# UWB_R_v1_4.net
KiCad netlist of a schematic drawn in Altium Designer
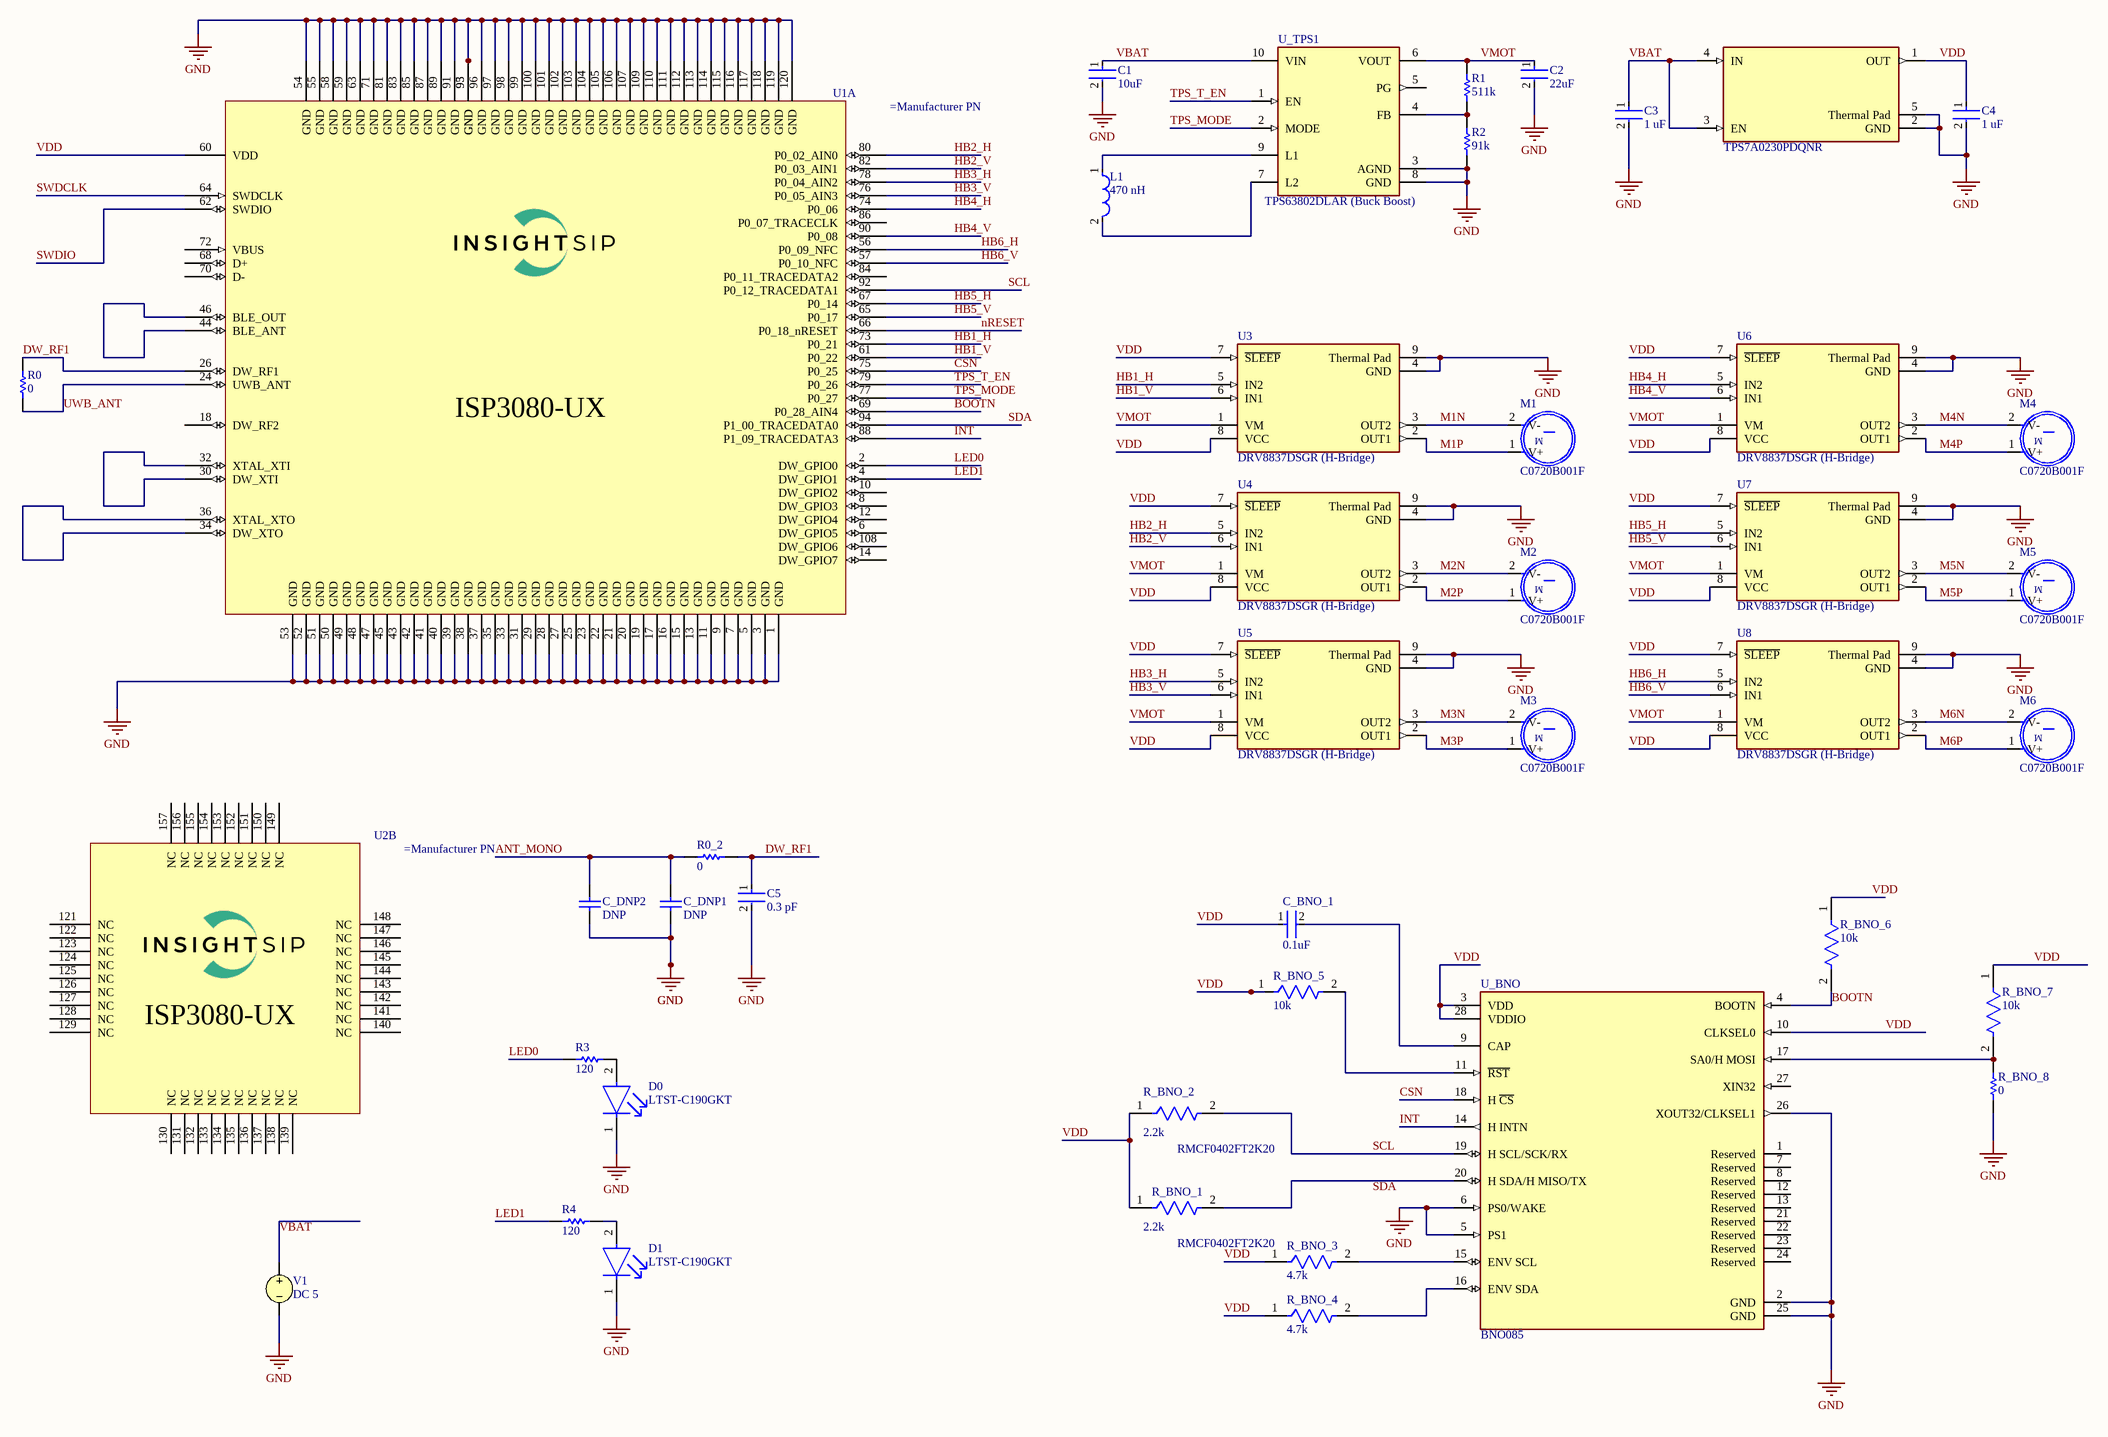
[diagram p0: UWB_R_v1.4.SchDoc]

(export (version "E")
  (design (tool "Eeschema 10.0.6"))
  (components
    (comp (ref "C1")
      (value "10uF")
      (footprint "FP-CL05A106MP5NUNC-MFG")
      (description "CL05A106MP5NUNC CAP CER 10UF 10V X5R 0402")
      (fields
        (field (name "OCTOPART") "https://octopart.com/cl05a106mp5nunc-samsung-22457395")
        (field (name "TOLERANCE") "20%")
      )
      (libsource (lib "Altium Content Vault") (part "b4654b650e69147ec39a6b967a45e02"))
    )
    (comp (ref "C2")
      (value "22uF")
      (footprint "FP-GRM188-0_2-IPC_C")
      (fields (field (name "TOLERANCE") "20%"))
      (libsource (lib "Altium Content Vault") (part "11868f565c42a9108669ba33697ecf6"))
    )
    (comp (ref "C3")
      (value "1 uF")
      (footprint "FP-CL10-IPC_C")
      (description "CL10B105KP8NNNC Cap Ceramic 1uF 10V X7R ±10% Pad SMD 0603 +125°C T/R")
      (fields (field (name "TOLERANCE") "10%"))
      (libsource (lib "Altium Content Vault") (part "b4654b650e69147ec39a6b967a45e02"))
    )
    (comp (ref "C4")
      (value "1 uF")
      (footprint "FP-CL10-IPC_C")
      (description "CL10B105KP8NNNC Cap Ceramic 1uF 10V X7R ±10% Pad SMD 0603 +125°C T/R")
      (fields (field (name "TOLERANCE") "10%"))
      (libsource (lib "Altium Content Vault") (part "b4654b650e69147ec39a6b967a45e02"))
    )
    (comp (ref "C5")
      (value "0.3 pF")
      (footprint "FP-GRM033-0_03-IPC_B")
      (description "GRM0335C1ER30BA01D")
      (libsource (lib "Altium Content Vault") (part "b4654b650e69147ec39a6b967a45e02"))
    )
    (comp (ref "C_BNO_1")
      (value "0.1uF")
      (footprint "FP-0402B104K160CT-IPC_C")
      (description "CAP CER 0.1UF 16V X7R 0402 0402B104K160CT")
      (fields (field (name "TOLERANCE") "10%"))
      (libsource (lib "Altium Content Vault") (part "b4654b650e69147ec39a6b967a45e02"))
    )
    (comp (ref "C_DNP1")
      (value "DNP")
      (footprint "CAPC1005X56X25NL10T15")
      (fields
        (field (name "PART NUMBER") "04025A180KAT2A")
        (field (name "MANUFACTURER") "AVX Interconnect / Elco")
      )
      (libsource (lib "Altium Content Vault") (part "CAP"))
    )
    (comp (ref "C_DNP2")
      (value "DNP")
      (footprint "CAPC1005X56X25NL10T15")
      (fields
        (field (name "PART NUMBER") "04025A180KAT2A")
        (field (name "MANUFACTURER") "AVX Interconnect / Elco")
      )
      (libsource (lib "Altium Content Vault") (part "CAP"))
    )
    (comp (ref "D0")
      (value "LTST-C190GKT")
      (footprint "FP-LTST-C190GKT-MFG")
      (description "LED GREEN CLEAR CHIP SMD")
      (fields (field (name "VOLTAGE") "2V"))
      (libsource (lib "Altium Content Vault") (part "8706943c75ba83719d021d2fdc84c58"))
    )
    (comp (ref "D1")
      (value "LTST-C190GKT")
      (footprint "FP-LTST-C190GKT-MFG")
      (description "LED GREEN CLEAR CHIP SMD")
      (fields (field (name "VOLTAGE") "2V"))
      (libsource (lib "Altium Content Vault") (part "8706943c75ba83719d021d2fdc84c58"))
    )
    (comp (ref "L1")
      (value "470 nH")
      (footprint "FP-CIGT201610-MFG")
      (description "CIGT201610EHR47MNE FIXED IND 470NH 4.8A 22MOHM SMD")
      (fields (field (name "TOLERANCE") "20%"))
      (libsource (lib "Altium Content Vault") (part "725321dda6339637d4d059423bc1c3c"))
    )
    (comp (ref "M1")
      (value "C0720B001F")
      (footprint "XDCR_C0720B001F")
      (description "DC Motor Vibration, ERM 10000 RPM 3VDC")
      (fields (field (name "MF") "Jinlong Machinery"))
      (libsource (lib "C0720B001F") (part "C0720B001F"))
    )
    (comp (ref "M2")
      (value "C0720B001F")
      (footprint "XDCR_C0720B001F")
      (description "DC Motor Vibration, ERM 10000 RPM 3VDC")
      (fields (field (name "MF") "Jinlong Machinery"))
      (libsource (lib "C0720B001F") (part "C0720B001F"))
    )
    (comp (ref "M3")
      (value "C0720B001F")
      (footprint "XDCR_C0720B001F")
      (description "DC Motor Vibration, ERM 10000 RPM 3VDC")
      (fields (field (name "MF") "Jinlong Machinery"))
      (libsource (lib "C0720B001F") (part "C0720B001F"))
    )
    (comp (ref "M4")
      (value "C0720B001F")
      (footprint "XDCR_C0720B001F")
      (description "DC Motor Vibration, ERM 10000 RPM 3VDC")
      (fields (field (name "MF") "Jinlong Machinery"))
      (libsource (lib "C0720B001F") (part "C0720B001F"))
    )
    (comp (ref "M5")
      (value "C0720B001F")
      (footprint "XDCR_C0720B001F")
      (description "DC Motor Vibration, ERM 10000 RPM 3VDC")
      (fields (field (name "MF") "Jinlong Machinery"))
      (libsource (lib "C0720B001F") (part "C0720B001F"))
    )
    (comp (ref "M6")
      (value "C0720B001F")
      (footprint "XDCR_C0720B001F")
      (description "DC Motor Vibration, ERM 10000 RPM 3VDC")
      (fields (field (name "MF") "Jinlong Machinery"))
      (libsource (lib "C0720B001F") (part "C0720B001F"))
    )
    (comp (ref "R0")
      (value "0")
      (footprint "RESC1005X40X25NL05T10")
      (description "RC0402JR-070RL")
      (fields (field (name "MANUFACTURER") "Yageo / Phycomp"))
      (libsource (lib "Altium Content Vault") (part "RES"))
    )
    (comp (ref "R0_2")
      (value "0")
      (footprint "RESC1005X40X25NL05T10")
      (description "RC0402JR-070RL")
      (fields (field (name "MANUFACTURER") "Yageo / Phycomp"))
      (libsource (lib "Altium Content Vault") (part "RES"))
    )
    (comp (ref "R1")
      (value "511k")
      (footprint "RESC1608X55X25ML10T15")
      (description "RC0603FR-07511KL")
      (fields (field (name "MANUFACTURER") "Yageo"))
      (libsource (lib "Altium Content Vault") (part "RES"))
    )
    (comp (ref "R2")
      (value "91k")
      (footprint "RESC0603X26X15NL03T05")
      (description "ERJ1GNF9102C")
      (fields (field (name "MANUFACTURER") "Panasonic"))
      (libsource (lib "Altium Content Vault") (part "RES"))
    )
    (comp (ref "R3")
      (value "120")
      (footprint "RESC2013X50X40ML20T20")
      (description "RG2012N-121-W-T1")
      (fields (field (name "MANUFACTURER") "Susumu"))
      (libsource (lib "Altium Content Vault") (part "RES"))
    )
    (comp (ref "R4")
      (value "120")
      (footprint "RESC2013X50X40ML20T20")
      (description "RG2012N-121-W-T1")
      (fields (field (name "MANUFACTURER") "Susumu"))
      (libsource (lib "Altium Content Vault") (part "RES"))
    )
    (comp (ref "R_BNO_1")
      (value "2.2k")
      (footprint "Stackpole_RMCF0402_IPC_A")
      (description "RES SMD 2.2K OHM 1% 1/16W 0402 RMCF0402FT2K20")
      (fields
        (field (name "PART NUMBER") "RMCF0402FT2K20")
        (field (name "DIGIKEY PART NUMBER") "RMCF0402FT2K20TR-ND")
      )
      (libsource (lib "EEConcierge") (part "RMCF0402FT2K20"))
    )
    (comp (ref "R_BNO_2")
      (value "2.2k")
      (footprint "Stackpole_RMCF0402_IPC_A")
      (description "RES SMD 2.2K OHM 1% 1/16W 0402 RMCF0402FT2K20")
      (fields
        (field (name "PART NUMBER") "RMCF0402FT2K20")
        (field (name "DIGIKEY PART NUMBER") "RMCF0402FT2K20TR-ND")
      )
      (libsource (lib "EEConcierge") (part "RMCF0402FT2K20"))
    )
    (comp (ref "R_BNO_3")
      (value "4.7k")
      (footprint "FP-RC0402-0_4-MFG")
      (description "RC0402JR-074K7L")
      (fields (field (name "TOLERANCE") "5%"))
      (libsource (lib "Altium Content Vault") (part "RC0402JR-074K7L"))
    )
    (comp (ref "R_BNO_4")
      (value "4.7k")
      (footprint "FP-RC0402-0_4-MFG")
      (description "RC0402JR-074K7L")
      (fields (field (name "TOLERANCE") "5%"))
      (libsource (lib "Altium Content Vault") (part "RC0402JR-074K7L"))
    )
    (comp (ref "R_BNO_5")
      (value "10k")
      (footprint "FP-RC0603-0_55-IPC_C")
      (description "RES 10K OHM 1% 1/10W 0603\r\n\r\nRC0603FR-0710KL")
      (fields (field (name "TOLERANCE") "1%"))
      (libsource (lib "Altium Content Vault") (part "1029c3af85768c4190bb7ad29bc67b5"))
    )
    (comp (ref "R_BNO_6")
      (value "10k")
      (footprint "FP-RC0603-0_55-IPC_C")
      (description "RES 10K OHM 1% 1/10W 0603\r\n\r\nRC0603FR-0710KL")
      (fields (field (name "TOLERANCE") "1%"))
      (libsource (lib "Altium Content Vault") (part "1029c3af85768c4190bb7ad29bc67b5"))
    )
    (comp (ref "R_BNO_7")
      (value "10k")
      (footprint "FP-RC0603-0_55-IPC_C")
      (description "RES 10K OHM 1% 1/10W 0603\r\n\r\nRC0603FR-0710KL")
      (fields (field (name "TOLERANCE") "1%"))
      (libsource (lib "Altium Content Vault") (part "1029c3af85768c4190bb7ad29bc67b5"))
    )
    (comp (ref "R_BNO_8")
      (value "0")
      (footprint "RESC1005X40X25NL05T10")
      (description "RC0402JR-070RL")
      (fields (field (name "MANUFACTURER") "Yageo / Phycomp"))
      (libsource (lib "Altium Content Vault") (part "RES"))
    )
    (comp (ref "TPS7A0230PDQNR")
      (value "TPS7A0230PDQNR")
      (footprint "Texas_Instruments_DQN0004A_MFG")
      (description "Linear Voltage Regulator IC, 1 Output, 6-1.5 V to 0.8-5 V (Fixed) Output, 200mA, 4-X2SON (1x1)")
      (fields
        (field (name "DIGIKEY PART NUMBER") "296-TPS7A0230PDQNRCT-ND")
        (field (name "MANUFACTURER") "Texas Instruments")
      )
      (libsource (lib "EEConcierge") (part "TPS7A0230PDQNR"))
    )
    (comp (ref "U1")
      (value "~")
      (footprint "ISP3080-UX")
      (description "BLE & UWB module (Revision C)")
      (libsource (lib "ISP3080C") (part "ISP3080-UX"))
    )
    (comp (ref "U2")
      (value "~")
      (description "BLE & UWB module (Revision C)")
      (libsource (lib "ISP3080C") (part "ISP3080-UX"))
    )
    (comp (ref "U3")
      (value "DRV8837DSGR (H-Bridge)")
      (footprint "FP-DSG0008A-MFG")
      (description "IC MOTOR DRIVER PAR 8WSON")
      (fields
        (field (name "MANUFACTURER PART NUMBER") "DRV8837DSGR")
        (field (name "MANUFACTURER") "Texas Instruments")
      )
      (libsource (lib "Altium Content Vault") (part "0edabe62f55b79d65ef7cb8a22a7164"))
    )
    (comp (ref "U4")
      (value "DRV8837DSGR (H-Bridge)")
      (footprint "FP-DSG0008A-MFG")
      (description "IC MOTOR DRIVER PAR 8WSON")
      (fields
        (field (name "MANUFACTURER PART NUMBER") "DRV8837DSGR")
        (field (name "MANUFACTURER") "Texas Instruments")
      )
      (libsource (lib "Altium Content Vault") (part "0edabe62f55b79d65ef7cb8a22a7164"))
    )
    (comp (ref "U5")
      (value "DRV8837DSGR (H-Bridge)")
      (footprint "FP-DSG0008A-MFG")
      (description "IC MOTOR DRIVER PAR 8WSON")
      (fields
        (field (name "MANUFACTURER PART NUMBER") "DRV8837DSGR")
        (field (name "MANUFACTURER") "Texas Instruments")
      )
      (libsource (lib "Altium Content Vault") (part "0edabe62f55b79d65ef7cb8a22a7164"))
    )
    (comp (ref "U6")
      (value "DRV8837DSGR (H-Bridge)")
      (footprint "FP-DSG0008A-MFG")
      (description "IC MOTOR DRIVER PAR 8WSON")
      (fields
        (field (name "MANUFACTURER PART NUMBER") "DRV8837DSGR")
        (field (name "MANUFACTURER") "Texas Instruments")
      )
      (libsource (lib "Altium Content Vault") (part "0edabe62f55b79d65ef7cb8a22a7164"))
    )
    (comp (ref "U7")
      (value "DRV8837DSGR (H-Bridge)")
      (footprint "FP-DSG0008A-MFG")
      (description "IC MOTOR DRIVER PAR 8WSON")
      (fields
        (field (name "MANUFACTURER PART NUMBER") "DRV8837DSGR")
        (field (name "MANUFACTURER") "Texas Instruments")
      )
      (libsource (lib "Altium Content Vault") (part "0edabe62f55b79d65ef7cb8a22a7164"))
    )
    (comp (ref "U8")
      (value "DRV8837DSGR (H-Bridge)")
      (footprint "FP-DSG0008A-MFG")
      (description "IC MOTOR DRIVER PAR 8WSON")
      (fields
        (field (name "MANUFACTURER PART NUMBER") "DRV8837DSGR")
        (field (name "MANUFACTURER") "Texas Instruments")
      )
      (libsource (lib "Altium Content Vault") (part "0edabe62f55b79d65ef7cb8a22a7164"))
    )
    (comp (ref "U_BNO")
      (value "BNO085")
      (footprint "FP-BNO085-MFG")
      (description "IMU ACCEL/GYRO/MAG I2C 32BIT")
      (fields
        (field (name "OCTOPART") "https://octopart.com/bno085-hillcrest+laboratories-92813482")
        (field (name "MANUFACTURER") "Hillcrest Laboratories, Inc.")
      )
      (libsource (lib "Altium Content Vault") (part "87552c951d161a888c2c69b58ce40bc"))
    )
    (comp (ref "U_TPS1")
      (value "TPS63802DLAR (Buck Boost)")
      (footprint "FP-DLA0010A-MFG")
      (description "IC POWER MANAGEMENT")
      (fields
        (field (name "MANUFACTURER PART NUMBER") "TPS63802DLAR")
        (field (name "OCTOPART") "https://octopart.com/tps63802dlar-texas+instruments-97359678")
      )
      (libsource (lib "Altium Content Vault") (part "f9a6115c6bf72e8ba457236a565d59e"))
    )
    (comp (ref "V1")
      (value "DC 5")
      (description "Voltage Source")
      (fields (field (name "PUBLISHER") "Altium Limited"))
      (libsource (lib "Simulation Generic Components") (part "VSRC"))
    )
  )
  (nets
    (net (code "1") (name "/ANT_MONO") (class "Default")
      (node (ref "C_DNP1") (pin "2") (pinfunction "2_2") (pintype "passive"))
      (node (ref "C_DNP2") (pin "2") (pinfunction "2_2") (pintype "passive"))
      (node (ref "R0_2") (pin "2") (pinfunction "2_2") (pintype "passive"))
    )
    (net (code "2") (name "/BOOTN") (class "Default")
      (node (ref "R_BNO_6") (pin "2") (pinfunction "2_2") (pintype "passive"))
      (node (ref "U1") (pin "69") (pinfunction "P0_28_AIN4_69") (pintype "bidirectional"))
      (node (ref "U_BNO") (pin "4") (pinfunction "BOOTN_4") (pintype "input"))
    )
    (net (code "3") (name "/CSN") (class "Default")
      (node (ref "U1") (pin "75") (pinfunction "P0_25_75") (pintype "bidirectional"))
      (node (ref "U_BNO") (pin "18") (pinfunction "H_~{CS}_18") (pintype "input"))
    )
    (net (code "4") (name "/DW_RF1") (class "Default")
      (node (ref "C5") (pin "1") (pinfunction "1_1") (pintype "passive"))
      (node (ref "R0") (pin "2") (pinfunction "2_2") (pintype "passive"))
      (node (ref "R0_2") (pin "1") (pinfunction "1_1") (pintype "passive"))
      (node (ref "U1") (pin "26") (pinfunction "DW_RF1_26") (pintype "bidirectional"))
    )
    (net (code "5") (name "/HB1_H") (class "Default")
      (node (ref "U1") (pin "73") (pinfunction "P0_21_73") (pintype "bidirectional"))
      (node (ref "U3") (pin "5") (pinfunction "IN2_5") (pintype "input"))
    )
    (net (code "6") (name "/HB1_V") (class "Default")
      (node (ref "U1") (pin "61") (pinfunction "P0_22_61") (pintype "bidirectional"))
      (node (ref "U3") (pin "6") (pinfunction "IN1_6") (pintype "input"))
    )
    (net (code "7") (name "/HB2_H") (class "Default")
      (node (ref "U1") (pin "80") (pinfunction "P0_02_AIN0_80") (pintype "bidirectional"))
      (node (ref "U4") (pin "5") (pinfunction "IN2_5") (pintype "input"))
    )
    (net (code "8") (name "/HB2_V") (class "Default")
      (node (ref "U1") (pin "82") (pinfunction "P0_03_AIN1_82") (pintype "bidirectional"))
      (node (ref "U4") (pin "6") (pinfunction "IN1_6") (pintype "input"))
    )
    (net (code "9") (name "/HB3_H") (class "Default")
      (node (ref "U1") (pin "78") (pinfunction "P0_04_AIN2_78") (pintype "bidirectional"))
      (node (ref "U5") (pin "5") (pinfunction "IN2_5") (pintype "input"))
    )
    (net (code "10") (name "/HB3_V") (class "Default")
      (node (ref "U1") (pin "76") (pinfunction "P0_05_AIN3_76") (pintype "bidirectional"))
      (node (ref "U5") (pin "6") (pinfunction "IN1_6") (pintype "input"))
    )
    (net (code "11") (name "/HB4_H") (class "Default")
      (node (ref "U1") (pin "74") (pinfunction "P0_06_74") (pintype "bidirectional"))
      (node (ref "U6") (pin "5") (pinfunction "IN2_5") (pintype "input"))
    )
    (net (code "12") (name "/HB4_V") (class "Default")
      (node (ref "U1") (pin "90") (pinfunction "P0_08_90") (pintype "bidirectional"))
      (node (ref "U6") (pin "6") (pinfunction "IN1_6") (pintype "input"))
    )
    (net (code "13") (name "/HB5_H") (class "Default")
      (node (ref "U1") (pin "67") (pinfunction "P0_14_67") (pintype "bidirectional"))
      (node (ref "U7") (pin "5") (pinfunction "IN2_5") (pintype "input"))
    )
    (net (code "14") (name "/HB5_V") (class "Default")
      (node (ref "U1") (pin "65") (pinfunction "P0_17_65") (pintype "bidirectional"))
      (node (ref "U7") (pin "6") (pinfunction "IN1_6") (pintype "input"))
    )
    (net (code "15") (name "/HB6_H") (class "Default")
      (node (ref "U1") (pin "56") (pinfunction "P0_09_NFC_56") (pintype "bidirectional"))
      (node (ref "U8") (pin "5") (pinfunction "IN2_5") (pintype "input"))
    )
    (net (code "16") (name "/HB6_V") (class "Default")
      (node (ref "U1") (pin "57") (pinfunction "P0_10_NFC_57") (pintype "bidirectional"))
      (node (ref "U8") (pin "6") (pinfunction "IN1_6") (pintype "input"))
    )
    (net (code "17") (name "/INT") (class "Default")
      (node (ref "U1") (pin "88") (pinfunction "P1_09_TRACEDATA3_88") (pintype "bidirectional"))
      (node (ref "U_BNO") (pin "14") (pinfunction "H_INTN_14") (pintype "output"))
    )
    (net (code "18") (name "/LED0") (class "Default")
      (node (ref "R3") (pin "1") (pinfunction "1_1") (pintype "passive"))
      (node (ref "U1") (pin "2") (pinfunction "DW_GPIO0_2") (pintype "bidirectional"))
    )
    (net (code "19") (name "/LED1") (class "Default")
      (node (ref "R4") (pin "1") (pinfunction "1_1") (pintype "passive"))
      (node (ref "U1") (pin "4") (pinfunction "DW_GPIO1_4") (pintype "bidirectional"))
    )
    (net (code "20") (name "/M1N") (class "Default")
      (node (ref "M1") (pin "2") (pinfunction "V-_2") (pintype "power_in"))
      (node (ref "U3") (pin "3") (pinfunction "OUT2_3") (pintype "output"))
    )
    (net (code "21") (name "/M1P") (class "Default")
      (node (ref "M1") (pin "1") (pinfunction "V+_1") (pintype "power_in"))
      (node (ref "U3") (pin "2") (pinfunction "OUT1_2") (pintype "output"))
    )
    (net (code "22") (name "/M2N") (class "Default")
      (node (ref "M2") (pin "2") (pinfunction "V-_2") (pintype "power_in"))
      (node (ref "U4") (pin "3") (pinfunction "OUT2_3") (pintype "output"))
    )
    (net (code "23") (name "/M2P") (class "Default")
      (node (ref "M2") (pin "1") (pinfunction "V+_1") (pintype "power_in"))
      (node (ref "U4") (pin "2") (pinfunction "OUT1_2") (pintype "output"))
    )
    (net (code "24") (name "/M3N") (class "Default")
      (node (ref "M3") (pin "2") (pinfunction "V-_2") (pintype "power_in"))
      (node (ref "U5") (pin "3") (pinfunction "OUT2_3") (pintype "output"))
    )
    (net (code "25") (name "/M3P") (class "Default")
      (node (ref "M3") (pin "1") (pinfunction "V+_1") (pintype "power_in"))
      (node (ref "U5") (pin "2") (pinfunction "OUT1_2") (pintype "output"))
    )
    (net (code "26") (name "/M4N") (class "Default")
      (node (ref "M4") (pin "2") (pinfunction "V-_2") (pintype "power_in"))
      (node (ref "U6") (pin "3") (pinfunction "OUT2_3") (pintype "output"))
    )
    (net (code "27") (name "/M4P") (class "Default")
      (node (ref "M4") (pin "1") (pinfunction "V+_1") (pintype "power_in"))
      (node (ref "U6") (pin "2") (pinfunction "OUT1_2") (pintype "output"))
    )
    (net (code "28") (name "/M5N") (class "Default")
      (node (ref "M5") (pin "2") (pinfunction "V-_2") (pintype "power_in"))
      (node (ref "U7") (pin "3") (pinfunction "OUT2_3") (pintype "output"))
    )
    (net (code "29") (name "/M5P") (class "Default")
      (node (ref "M5") (pin "1") (pinfunction "V+_1") (pintype "power_in"))
      (node (ref "U7") (pin "2") (pinfunction "OUT1_2") (pintype "output"))
    )
    (net (code "30") (name "/M6N") (class "Default")
      (node (ref "M6") (pin "2") (pinfunction "V-_2") (pintype "power_in"))
      (node (ref "U8") (pin "3") (pinfunction "OUT2_3") (pintype "output"))
    )
    (net (code "31") (name "/M6P") (class "Default")
      (node (ref "M6") (pin "1") (pinfunction "V+_1") (pintype "power_in"))
      (node (ref "U8") (pin "2") (pinfunction "OUT1_2") (pintype "output"))
    )
    (net (code "32") (name "/SCL") (class "Default")
      (node (ref "R_BNO_2") (pin "2") (pinfunction "2_2") (pintype "passive"))
      (node (ref "U1") (pin "92") (pinfunction "P0_12_TRACEDATA1_92") (pintype "bidirectional"))
      (node (ref "U_BNO") (pin "19") (pinfunction "H_SCL/SCK/RX_19") (pintype "bidirectional"))
    )
    (net (code "33") (name "/SDA") (class "Default")
      (node (ref "U1") (pin "94") (pinfunction "P1_00_TRACEDATA0_94") (pintype "bidirectional"))
    )
    (net (code "34") (name "/SWDCLK") (class "Default")
      (node (ref "U1") (pin "64") (pinfunction "SWDCLK_64") (pintype "input"))
    )
    (net (code "35") (name "/SWDIO") (class "Default")
      (node (ref "U1") (pin "62") (pinfunction "SWDIO_62") (pintype "bidirectional"))
    )
    (net (code "36") (name "/TPS_MODE") (class "Default")
      (node (ref "U1") (pin "77") (pinfunction "P0_27_77") (pintype "bidirectional"))
      (node (ref "U_TPS1") (pin "2") (pinfunction "MODE_2") (pintype "input"))
    )
    (net (code "37") (name "/TPS_T_EN") (class "Default")
      (node (ref "U1") (pin "79") (pinfunction "P0_26_79") (pintype "bidirectional"))
      (node (ref "U_TPS1") (pin "1") (pinfunction "EN_1") (pintype "input"))
    )
    (net (code "38") (name "/UWB_ANT") (class "Default")
      (node (ref "R0") (pin "1") (pinfunction "1_1") (pintype "passive"))
      (node (ref "U1") (pin "24") (pinfunction "UWB_ANT_24") (pintype "bidirectional"))
    )
    (net (code "39") (name "/VBAT") (class "Default")
      (node (ref "C1") (pin "1") (pinfunction "1_1") (pintype "passive"))
      (node (ref "C3") (pin "1") (pinfunction "1_1") (pintype "passive"))
      (node (ref "TPS7A0230PDQNR") (pin "3") (pinfunction "EN_3") (pintype "input"))
      (node (ref "TPS7A0230PDQNR") (pin "4") (pinfunction "IN_4") (pintype "input"))
      (node (ref "U_TPS1") (pin "10") (pinfunction "VIN_10") (pintype "power_in"))
      (node (ref "V1") (pin "1") (pinfunction "1_1") (pintype "passive"))
    )
    (net (code "40") (name "/VDD") (class "Default")
      (node (ref "C4") (pin "1") (pinfunction "1_1") (pintype "passive"))
      (node (ref "C_BNO_1") (pin "1") (pinfunction "1_1") (pintype "passive"))
      (node (ref "R_BNO_1") (pin "1") (pinfunction "1_1") (pintype "passive"))
      (node (ref "R_BNO_2") (pin "1") (pinfunction "1_1") (pintype "passive"))
      (node (ref "R_BNO_3") (pin "1") (pinfunction "1_1") (pintype "passive"))
      (node (ref "R_BNO_4") (pin "1") (pinfunction "1_1") (pintype "passive"))
      (node (ref "R_BNO_5") (pin "1") (pinfunction "1_1") (pintype "passive"))
      (node (ref "R_BNO_6") (pin "1") (pinfunction "1_1") (pintype "passive"))
      (node (ref "R_BNO_7") (pin "1") (pinfunction "1_1") (pintype "passive"))
      (node (ref "TPS7A0230PDQNR") (pin "1") (pinfunction "OUT_1") (pintype "output"))
      (node (ref "U1") (pin "60") (pinfunction "VDD_60") (pintype "power_in"))
      (node (ref "U3") (pin "7") (pinfunction "~{SLEEP}_7") (pintype "input"))
      (node (ref "U3") (pin "8") (pinfunction "VCC_8") (pintype "power_in"))
      (node (ref "U4") (pin "7") (pinfunction "~{SLEEP}_7") (pintype "input"))
      (node (ref "U4") (pin "8") (pinfunction "VCC_8") (pintype "power_in"))
      (node (ref "U5") (pin "7") (pinfunction "~{SLEEP}_7") (pintype "input"))
      (node (ref "U5") (pin "8") (pinfunction "VCC_8") (pintype "power_in"))
      (node (ref "U6") (pin "7") (pinfunction "~{SLEEP}_7") (pintype "input"))
      (node (ref "U6") (pin "8") (pinfunction "VCC_8") (pintype "power_in"))
      (node (ref "U7") (pin "7") (pinfunction "~{SLEEP}_7") (pintype "input"))
      (node (ref "U7") (pin "8") (pinfunction "VCC_8") (pintype "power_in"))
      (node (ref "U8") (pin "7") (pinfunction "~{SLEEP}_7") (pintype "input"))
      (node (ref "U8") (pin "8") (pinfunction "VCC_8") (pintype "power_in"))
      (node (ref "U_BNO") (pin "10") (pinfunction "CLKSEL0_10") (pintype "input"))
      (node (ref "U_BNO") (pin "28") (pinfunction "VDDIO_28") (pintype "power_in"))
      (node (ref "U_BNO") (pin "3") (pinfunction "VDD_3") (pintype "power_in"))
    )
    (net (code "41") (name "/VMOT") (class "Default")
      (node (ref "C2") (pin "1") (pinfunction "1_1") (pintype "passive"))
      (node (ref "R1") (pin "2") (pinfunction "2_2") (pintype "passive"))
      (node (ref "U3") (pin "1") (pinfunction "VM_1") (pintype "power_in"))
      (node (ref "U4") (pin "1") (pinfunction "VM_1") (pintype "power_in"))
      (node (ref "U5") (pin "1") (pinfunction "VM_1") (pintype "power_in"))
      (node (ref "U6") (pin "1") (pinfunction "VM_1") (pintype "power_in"))
      (node (ref "U7") (pin "1") (pinfunction "VM_1") (pintype "power_in"))
      (node (ref "U8") (pin "1") (pinfunction "VM_1") (pintype "power_in"))
      (node (ref "U_TPS1") (pin "6") (pinfunction "VOUT_6") (pintype "power_in"))
    )
    (net (code "42") (name "/nRESET") (class "Default")
      (node (ref "U1") (pin "66") (pinfunction "P0_18_nRESET_66") (pintype "bidirectional"))
    )
    (net (code "43") (name "GND") (class "Default")
      (node (ref "C1") (pin "2") (pinfunction "2_2") (pintype "passive"))
      (node (ref "C2") (pin "2") (pinfunction "2_2") (pintype "passive"))
      (node (ref "C3") (pin "2") (pinfunction "2_2") (pintype "passive"))
      (node (ref "C4") (pin "2") (pinfunction "2_2") (pintype "passive"))
      (node (ref "C5") (pin "2") (pinfunction "2_2") (pintype "passive"))
      (node (ref "C_DNP1") (pin "1") (pinfunction "1_1") (pintype "passive"))
      (node (ref "C_DNP2") (pin "1") (pinfunction "1_1") (pintype "passive"))
      (node (ref "D0") (pin "1") (pinfunction "C_1") (pintype "passive"))
      (node (ref "D1") (pin "1") (pinfunction "C_1") (pintype "passive"))
      (node (ref "R2") (pin "1") (pinfunction "1_1") (pintype "passive"))
      (node (ref "R_BNO_8") (pin "2") (pinfunction "2_2") (pintype "passive"))
      (node (ref "TPS7A0230PDQNR") (pin "2") (pinfunction "GND_2") (pintype "power_in"))
      (node (ref "TPS7A0230PDQNR") (pin "5") (pinfunction "Thermal_Pad_5") (pintype "power_in"))
      (node (ref "U1") (pin "1") (pinfunction "GND_1") (pintype "power_in"))
      (node (ref "U1") (pin "100") (pinfunction "GND_100") (pintype "power_in"))
      (node (ref "U1") (pin "101") (pinfunction "GND_101") (pintype "power_in"))
      (node (ref "U1") (pin "102") (pinfunction "GND_102") (pintype "power_in"))
      (node (ref "U1") (pin "103") (pinfunction "GND_103") (pintype "power_in"))
      (node (ref "U1") (pin "104") (pinfunction "GND_104") (pintype "power_in"))
      (node (ref "U1") (pin "105") (pinfunction "GND_105") (pintype "power_in"))
      (node (ref "U1") (pin "106") (pinfunction "GND_106") (pintype "power_in"))
      (node (ref "U1") (pin "107") (pinfunction "GND_107") (pintype "power_in"))
      (node (ref "U1") (pin "109") (pinfunction "GND_109") (pintype "power_in"))
      (node (ref "U1") (pin "11") (pinfunction "GND_11") (pintype "power_in"))
      (node (ref "U1") (pin "110") (pinfunction "GND_110") (pintype "power_in"))
      (node (ref "U1") (pin "111") (pinfunction "GND_111") (pintype "power_in"))
      (node (ref "U1") (pin "112") (pinfunction "GND_112") (pintype "power_in"))
      (node (ref "U1") (pin "113") (pinfunction "GND_113") (pintype "power_in"))
      (node (ref "U1") (pin "114") (pinfunction "GND_114") (pintype "power_in"))
      (node (ref "U1") (pin "115") (pinfunction "GND_115") (pintype "power_in"))
      (node (ref "U1") (pin "116") (pinfunction "GND_116") (pintype "power_in"))
      (node (ref "U1") (pin "117") (pinfunction "GND_117") (pintype "power_in"))
      (node (ref "U1") (pin "118") (pinfunction "GND_118") (pintype "power_in"))
      (node (ref "U1") (pin "119") (pinfunction "GND_119") (pintype "power_in"))
      (node (ref "U1") (pin "120") (pinfunction "GND_120") (pintype "power_in"))
      (node (ref "U1") (pin "13") (pinfunction "GND_13") (pintype "power_in"))
      (node (ref "U1") (pin "15") (pinfunction "GND_15") (pintype "power_in"))
      (node (ref "U1") (pin "16") (pinfunction "GND_16") (pintype "power_in"))
      (node (ref "U1") (pin "17") (pinfunction "GND_17") (pintype "power_in"))
      (node (ref "U1") (pin "19") (pinfunction "GND_19") (pintype "power_in"))
      (node (ref "U1") (pin "20") (pinfunction "GND_20") (pintype "power_in"))
      (node (ref "U1") (pin "21") (pinfunction "GND_21") (pintype "power_in"))
      (node (ref "U1") (pin "22") (pinfunction "GND_22") (pintype "power_in"))
      (node (ref "U1") (pin "23") (pinfunction "GND_23") (pintype "power_in"))
      (node (ref "U1") (pin "25") (pinfunction "GND_25") (pintype "power_in"))
      (node (ref "U1") (pin "27") (pinfunction "GND_27") (pintype "power_in"))
      (node (ref "U1") (pin "28") (pinfunction "GND_28") (pintype "power_in"))
      (node (ref "U1") (pin "29") (pinfunction "GND_29") (pintype "power_in"))
      (node (ref "U1") (pin "3") (pinfunction "GND_3") (pintype "power_in"))
      (node (ref "U1") (pin "31") (pinfunction "GND_31") (pintype "power_in"))
      (node (ref "U1") (pin "33") (pinfunction "GND_33") (pintype "power_in"))
      (node (ref "U1") (pin "35") (pinfunction "GND_35") (pintype "power_in"))
      (node (ref "U1") (pin "37") (pinfunction "GND_37") (pintype "power_in"))
      (node (ref "U1") (pin "38") (pinfunction "GND_38") (pintype "power_in"))
      (node (ref "U1") (pin "39") (pinfunction "GND_39") (pintype "power_in"))
      (node (ref "U1") (pin "40") (pinfunction "GND_40") (pintype "power_in"))
      (node (ref "U1") (pin "41") (pinfunction "GND_41") (pintype "power_in"))
      (node (ref "U1") (pin "42") (pinfunction "GND_42") (pintype "power_in"))
      (node (ref "U1") (pin "43") (pinfunction "GND_43") (pintype "power_in"))
      (node (ref "U1") (pin "45") (pinfunction "GND_45") (pintype "power_in"))
      (node (ref "U1") (pin "47") (pinfunction "GND_47") (pintype "power_in"))
      (node (ref "U1") (pin "48") (pinfunction "GND_48") (pintype "power_in"))
      (node (ref "U1") (pin "49") (pinfunction "GND_49") (pintype "power_in"))
      (node (ref "U1") (pin "5") (pinfunction "GND_5") (pintype "power_in"))
      (node (ref "U1") (pin "50") (pinfunction "GND_50") (pintype "power_in"))
      (node (ref "U1") (pin "51") (pinfunction "GND_51") (pintype "power_in"))
      (node (ref "U1") (pin "52") (pinfunction "GND_52") (pintype "power_in"))
      (node (ref "U1") (pin "53") (pinfunction "GND_53") (pintype "power_in"))
      (node (ref "U1") (pin "54") (pinfunction "GND_54") (pintype "power_in"))
      (node (ref "U1") (pin "55") (pinfunction "GND_55") (pintype "power_in"))
      (node (ref "U1") (pin "58") (pinfunction "GND_58") (pintype "power_in"))
      (node (ref "U1") (pin "59") (pinfunction "GND_59") (pintype "power_in"))
      (node (ref "U1") (pin "63") (pinfunction "GND_63") (pintype "power_in"))
      (node (ref "U1") (pin "7") (pinfunction "GND_7") (pintype "power_in"))
      (node (ref "U1") (pin "71") (pinfunction "GND_71") (pintype "power_in"))
      (node (ref "U1") (pin "81") (pinfunction "GND_81") (pintype "power_in"))
      (node (ref "U1") (pin "83") (pinfunction "GND_83") (pintype "power_in"))
      (node (ref "U1") (pin "85") (pinfunction "GND_85") (pintype "power_in"))
      (node (ref "U1") (pin "87") (pinfunction "GND_87") (pintype "power_in"))
      (node (ref "U1") (pin "89") (pinfunction "GND_89") (pintype "power_in"))
      (node (ref "U1") (pin "9") (pinfunction "GND_9") (pintype "power_in"))
      (node (ref "U1") (pin "91") (pinfunction "GND_91") (pintype "power_in"))
      (node (ref "U1") (pin "93") (pinfunction "GND_93") (pintype "power_in"))
      (node (ref "U1") (pin "95") (pinfunction "GND_95") (pintype "power_in"))
      (node (ref "U1") (pin "96") (pinfunction "GND_96") (pintype "power_in"))
      (node (ref "U1") (pin "97") (pinfunction "GND_97") (pintype "power_in"))
      (node (ref "U1") (pin "98") (pinfunction "GND_98") (pintype "power_in"))
      (node (ref "U1") (pin "99") (pinfunction "GND_99") (pintype "power_in"))
      (node (ref "U3") (pin "4") (pinfunction "GND_4") (pintype "power_in"))
      (node (ref "U3") (pin "9") (pinfunction "Thermal_Pad_9") (pintype "power_in"))
      (node (ref "U4") (pin "4") (pinfunction "GND_4") (pintype "power_in"))
      (node (ref "U4") (pin "9") (pinfunction "Thermal_Pad_9") (pintype "power_in"))
      (node (ref "U5") (pin "4") (pinfunction "GND_4") (pintype "power_in"))
      (node (ref "U5") (pin "9") (pinfunction "Thermal_Pad_9") (pintype "power_in"))
      (node (ref "U6") (pin "4") (pinfunction "GND_4") (pintype "power_in"))
      (node (ref "U6") (pin "9") (pinfunction "Thermal_Pad_9") (pintype "power_in"))
      (node (ref "U7") (pin "4") (pinfunction "GND_4") (pintype "power_in"))
      (node (ref "U7") (pin "9") (pinfunction "Thermal_Pad_9") (pintype "power_in"))
      (node (ref "U8") (pin "4") (pinfunction "GND_4") (pintype "power_in"))
      (node (ref "U8") (pin "9") (pinfunction "Thermal_Pad_9") (pintype "power_in"))
      (node (ref "U_BNO") (pin "2") (pinfunction "GND_2") (pintype "power_in"))
      (node (ref "U_BNO") (pin "25") (pinfunction "GND_25") (pintype "power_in"))
      (node (ref "U_BNO") (pin "26") (pinfunction "XOUT32/CLKSEL1_26") (pintype "output"))
      (node (ref "U_BNO") (pin "5") (pinfunction "PS1_5") (pintype "input"))
      (node (ref "U_BNO") (pin "6") (pinfunction "PS0/WAKE_6") (pintype "input"))
      (node (ref "U_TPS1") (pin "3") (pinfunction "AGND_3") (pintype "power_in"))
      (node (ref "U_TPS1") (pin "8") (pinfunction "GND_8") (pintype "power_in"))
      (node (ref "V1") (pin "2") (pinfunction "2_2") (pintype "passive"))
    )
    (net (code "44") (name "Net-(D0-A)") (class "Default")
      (node (ref "D0") (pin "2") (pinfunction "A_2") (pintype "passive"))
      (node (ref "R3") (pin "2") (pinfunction "2_2") (pintype "passive"))
    )
    (net (code "45") (name "Net-(D1-A)") (class "Default")
      (node (ref "D1") (pin "2") (pinfunction "A_2") (pintype "passive"))
      (node (ref "R4") (pin "2") (pinfunction "2_2") (pintype "passive"))
    )
    (net (code "46") (name "Net-(U1A-BLE_ANT)") (class "Default")
      (node (ref "U1") (pin "44") (pinfunction "BLE_ANT_44") (pintype "bidirectional"))
      (node (ref "U1") (pin "46") (pinfunction "BLE_OUT_46") (pintype "bidirectional"))
    )
    (net (code "47") (name "Net-(U1A-DW_XTI)") (class "Default")
      (node (ref "U1") (pin "30") (pinfunction "DW_XTI_30") (pintype "bidirectional"))
      (node (ref "U1") (pin "32") (pinfunction "XTAL_XTI_32") (pintype "bidirectional"))
    )
    (net (code "48") (name "Net-(U1A-DW_XTO)") (class "Default")
      (node (ref "U1") (pin "34") (pinfunction "DW_XTO_34") (pintype "bidirectional"))
      (node (ref "U1") (pin "36") (pinfunction "XTAL_XTO_36") (pintype "bidirectional"))
    )
    (net (code "49") (name "Net-(U_BNO-CAP)") (class "Default")
      (node (ref "C_BNO_1") (pin "2") (pinfunction "2_2") (pintype "passive"))
      (node (ref "U_BNO") (pin "9") (pinfunction "CAP_9") (pintype "passive"))
    )
    (net (code "50") (name "Net-(U_BNO-ENV_SCL)") (class "Default")
      (node (ref "R_BNO_3") (pin "2") (pinfunction "2_2") (pintype "passive"))
      (node (ref "U_BNO") (pin "15") (pinfunction "ENV_SCL_15") (pintype "bidirectional"))
    )
    (net (code "51") (name "Net-(U_BNO-ENV_SDA)") (class "Default")
      (node (ref "R_BNO_4") (pin "2") (pinfunction "2_2") (pintype "passive"))
      (node (ref "U_BNO") (pin "16") (pinfunction "ENV_SDA_16") (pintype "bidirectional"))
    )
    (net (code "52") (name "Net-(U_BNO-H_SDA{slash}H_MISO{slash}TX)") (class "Default")
      (node (ref "R_BNO_1") (pin "2") (pinfunction "2_2") (pintype "passive"))
      (node (ref "U_BNO") (pin "20") (pinfunction "H_SDA/H_MISO/TX_20") (pintype "bidirectional"))
    )
    (net (code "53") (name "Net-(U_BNO-SA0{slash}H_MOSI)") (class "Default")
      (node (ref "R_BNO_7") (pin "2") (pinfunction "2_2") (pintype "passive"))
      (node (ref "R_BNO_8") (pin "1") (pinfunction "1_1") (pintype "passive"))
      (node (ref "U_BNO") (pin "17") (pinfunction "SA0/H_MOSI_17") (pintype "input"))
    )
    (net (code "54") (name "Net-(U_BNO-~{RST})") (class "Default")
      (node (ref "R_BNO_5") (pin "2") (pinfunction "2_2") (pintype "passive"))
      (node (ref "U_BNO") (pin "11") (pinfunction "~{RST}_11") (pintype "input"))
    )
    (net (code "55") (name "Net-(U_TPS1-FB)") (class "Default")
      (node (ref "R1") (pin "1") (pinfunction "1_1") (pintype "passive"))
      (node (ref "R2") (pin "2") (pinfunction "2_2") (pintype "passive"))
      (node (ref "U_TPS1") (pin "4") (pinfunction "FB_4") (pintype "passive"))
    )
    (net (code "56") (name "Net-(U_TPS1-L1)") (class "Default")
      (node (ref "L1") (pin "1") (pinfunction "1_1") (pintype "passive"))
      (node (ref "U_TPS1") (pin "9") (pinfunction "L1_9") (pintype "passive"))
    )
    (net (code "57") (name "Net-(U_TPS1-L2)") (class "Default")
      (node (ref "L1") (pin "2") (pinfunction "2_2") (pintype "passive"))
      (node (ref "U_TPS1") (pin "7") (pinfunction "L2_7") (pintype "passive"))
    )
    (net (code "58") (name "unconnected-(U1A-D+-Pad68)") (class "Default")
      (node (ref "U1") (pin "68") (pinfunction "D+_68") (pintype "bidirectional"))
    )
    (net (code "59") (name "unconnected-(U1A-D--Pad70)") (class "Default")
      (node (ref "U1") (pin "70") (pinfunction "D-_70") (pintype "bidirectional"))
    )
    (net (code "60") (name "unconnected-(U1A-DW_GPIO2-Pad10)") (class "Default")
      (node (ref "U1") (pin "10") (pinfunction "DW_GPIO2_10") (pintype "bidirectional"))
    )
    (net (code "61") (name "unconnected-(U1A-DW_GPIO3-Pad8)") (class "Default")
      (node (ref "U1") (pin "8") (pinfunction "DW_GPIO3_8") (pintype "bidirectional"))
    )
    (net (code "62") (name "unconnected-(U1A-DW_GPIO4-Pad12)") (class "Default")
      (node (ref "U1") (pin "12") (pinfunction "DW_GPIO4_12") (pintype "bidirectional"))
    )
    (net (code "63") (name "unconnected-(U1A-DW_GPIO5-Pad6)") (class "Default")
      (node (ref "U1") (pin "6") (pinfunction "DW_GPIO5_6") (pintype "bidirectional"))
    )
    (net (code "64") (name "unconnected-(U1A-DW_GPIO6-Pad108)") (class "Default")
      (node (ref "U1") (pin "108") (pinfunction "DW_GPIO6_108") (pintype "bidirectional"))
    )
    (net (code "65") (name "unconnected-(U1A-DW_GPIO7-Pad14)") (class "Default")
      (node (ref "U1") (pin "14") (pinfunction "DW_GPIO7_14") (pintype "bidirectional"))
    )
    (net (code "66") (name "unconnected-(U1A-DW_RF2-Pad18)") (class "Default")
      (node (ref "U1") (pin "18") (pinfunction "DW_RF2_18") (pintype "bidirectional"))
    )
    (net (code "67") (name "unconnected-(U1A-P0_07_TRACECLK-Pad86)") (class "Default")
      (node (ref "U1") (pin "86") (pinfunction "P0_07_TRACECLK_86") (pintype "bidirectional"))
    )
    (net (code "68") (name "unconnected-(U1A-P0_11_TRACEDATA2-Pad84)") (class "Default")
      (node (ref "U1") (pin "84") (pinfunction "P0_11_TRACEDATA2_84") (pintype "bidirectional"))
    )
    (net (code "69") (name "unconnected-(U1A-VBUS-Pad72)") (class "Default")
      (node (ref "U1") (pin "72") (pinfunction "VBUS_72") (pintype "input"))
    )
    (net (code "70") (name "unconnected-(U2B-NC-Pad121)") (class "Default")
      (node (ref "U2") (pin "121") (pinfunction "NC_121") (pintype "passive"))
    )
    (net (code "71") (name "unconnected-(U2B-NC-Pad122)") (class "Default")
      (node (ref "U2") (pin "122") (pinfunction "NC_122") (pintype "passive"))
    )
    (net (code "72") (name "unconnected-(U2B-NC-Pad123)") (class "Default")
      (node (ref "U2") (pin "123") (pinfunction "NC_123") (pintype "passive"))
    )
    (net (code "73") (name "unconnected-(U2B-NC-Pad124)") (class "Default")
      (node (ref "U2") (pin "124") (pinfunction "NC_124") (pintype "passive"))
    )
    (net (code "74") (name "unconnected-(U2B-NC-Pad125)") (class "Default")
      (node (ref "U2") (pin "125") (pinfunction "NC_125") (pintype "passive"))
    )
    (net (code "75") (name "unconnected-(U2B-NC-Pad126)") (class "Default")
      (node (ref "U2") (pin "126") (pinfunction "NC_126") (pintype "passive"))
    )
    (net (code "76") (name "unconnected-(U2B-NC-Pad127)") (class "Default")
      (node (ref "U2") (pin "127") (pinfunction "NC_127") (pintype "passive"))
    )
    (net (code "77") (name "unconnected-(U2B-NC-Pad128)") (class "Default")
      (node (ref "U2") (pin "128") (pinfunction "NC_128") (pintype "passive"))
    )
    (net (code "78") (name "unconnected-(U2B-NC-Pad129)") (class "Default")
      (node (ref "U2") (pin "129") (pinfunction "NC_129") (pintype "passive"))
    )
    (net (code "79") (name "unconnected-(U2B-NC-Pad130)") (class "Default")
      (node (ref "U2") (pin "130") (pinfunction "NC_130") (pintype "passive"))
    )
    (net (code "80") (name "unconnected-(U2B-NC-Pad131)") (class "Default")
      (node (ref "U2") (pin "131") (pinfunction "NC_131") (pintype "passive"))
    )
    (net (code "81") (name "unconnected-(U2B-NC-Pad132)") (class "Default")
      (node (ref "U2") (pin "132") (pinfunction "NC_132") (pintype "passive"))
    )
    (net (code "82") (name "unconnected-(U2B-NC-Pad133)") (class "Default")
      (node (ref "U2") (pin "133") (pinfunction "NC_133") (pintype "passive"))
    )
    (net (code "83") (name "unconnected-(U2B-NC-Pad134)") (class "Default")
      (node (ref "U2") (pin "134") (pinfunction "NC_134") (pintype "passive"))
    )
    (net (code "84") (name "unconnected-(U2B-NC-Pad135)") (class "Default")
      (node (ref "U2") (pin "135") (pinfunction "NC_135") (pintype "passive"))
    )
    (net (code "85") (name "unconnected-(U2B-NC-Pad136)") (class "Default")
      (node (ref "U2") (pin "136") (pinfunction "NC_136") (pintype "passive"))
    )
    (net (code "86") (name "unconnected-(U2B-NC-Pad137)") (class "Default")
      (node (ref "U2") (pin "137") (pinfunction "NC_137") (pintype "passive"))
    )
    (net (code "87") (name "unconnected-(U2B-NC-Pad138)") (class "Default")
      (node (ref "U2") (pin "138") (pinfunction "NC_138") (pintype "passive"))
    )
    (net (code "88") (name "unconnected-(U2B-NC-Pad139)") (class "Default")
      (node (ref "U2") (pin "139") (pinfunction "NC_139") (pintype "passive"))
    )
    (net (code "89") (name "unconnected-(U2B-NC-Pad140)") (class "Default")
      (node (ref "U2") (pin "140") (pinfunction "NC_140") (pintype "passive"))
    )
    (net (code "90") (name "unconnected-(U2B-NC-Pad141)") (class "Default")
      (node (ref "U2") (pin "141") (pinfunction "NC_141") (pintype "passive"))
    )
    (net (code "91") (name "unconnected-(U2B-NC-Pad142)") (class "Default")
      (node (ref "U2") (pin "142") (pinfunction "NC_142") (pintype "passive"))
    )
    (net (code "92") (name "unconnected-(U2B-NC-Pad143)") (class "Default")
      (node (ref "U2") (pin "143") (pinfunction "NC_143") (pintype "passive"))
    )
    (net (code "93") (name "unconnected-(U2B-NC-Pad144)") (class "Default")
      (node (ref "U2") (pin "144") (pinfunction "NC_144") (pintype "passive"))
    )
    (net (code "94") (name "unconnected-(U2B-NC-Pad145)") (class "Default")
      (node (ref "U2") (pin "145") (pinfunction "NC_145") (pintype "passive"))
    )
    (net (code "95") (name "unconnected-(U2B-NC-Pad146)") (class "Default")
      (node (ref "U2") (pin "146") (pinfunction "NC_146") (pintype "passive"))
    )
    (net (code "96") (name "unconnected-(U2B-NC-Pad147)") (class "Default")
      (node (ref "U2") (pin "147") (pinfunction "NC_147") (pintype "passive"))
    )
    (net (code "97") (name "unconnected-(U2B-NC-Pad148)") (class "Default")
      (node (ref "U2") (pin "148") (pinfunction "NC_148") (pintype "passive"))
    )
    (net (code "98") (name "unconnected-(U2B-NC-Pad149)") (class "Default")
      (node (ref "U2") (pin "149") (pinfunction "NC_149") (pintype "passive"))
    )
    (net (code "99") (name "unconnected-(U2B-NC-Pad150)") (class "Default")
      (node (ref "U2") (pin "150") (pinfunction "NC_150") (pintype "passive"))
    )
    (net (code "100") (name "unconnected-(U2B-NC-Pad151)") (class "Default")
      (node (ref "U2") (pin "151") (pinfunction "NC_151") (pintype "passive"))
    )
    (net (code "101") (name "unconnected-(U2B-NC-Pad152)") (class "Default")
      (node (ref "U2") (pin "152") (pinfunction "NC_152") (pintype "passive"))
    )
    (net (code "102") (name "unconnected-(U2B-NC-Pad153)") (class "Default")
      (node (ref "U2") (pin "153") (pinfunction "NC_153") (pintype "passive"))
    )
    (net (code "103") (name "unconnected-(U2B-NC-Pad154)") (class "Default")
      (node (ref "U2") (pin "154") (pinfunction "NC_154") (pintype "passive"))
    )
    (net (code "104") (name "unconnected-(U2B-NC-Pad155)") (class "Default")
      (node (ref "U2") (pin "155") (pinfunction "NC_155") (pintype "passive"))
    )
    (net (code "105") (name "unconnected-(U2B-NC-Pad156)") (class "Default")
      (node (ref "U2") (pin "156") (pinfunction "NC_156") (pintype "passive"))
    )
    (net (code "106") (name "unconnected-(U2B-NC-Pad157)") (class "Default")
      (node (ref "U2") (pin "157") (pinfunction "NC_157") (pintype "passive"))
    )
    (net (code "107") (name "unconnected-(U_BNO-Reserved-Pad1)") (class "Default")
      (node (ref "U_BNO") (pin "1") (pinfunction "Reserved_1") (pintype "passive"))
    )
    (net (code "108") (name "unconnected-(U_BNO-Reserved-Pad7)") (class "Default")
      (node (ref "U_BNO") (pin "7") (pinfunction "Reserved_7") (pintype "passive"))
    )
    (net (code "109") (name "unconnected-(U_BNO-Reserved-Pad8)") (class "Default")
      (node (ref "U_BNO") (pin "8") (pinfunction "Reserved_8") (pintype "passive"))
    )
    (net (code "110") (name "unconnected-(U_BNO-Reserved-Pad12)") (class "Default")
      (node (ref "U_BNO") (pin "12") (pinfunction "Reserved_12") (pintype "passive"))
    )
    (net (code "111") (name "unconnected-(U_BNO-Reserved-Pad13)") (class "Default")
      (node (ref "U_BNO") (pin "13") (pinfunction "Reserved_13") (pintype "passive"))
    )
    (net (code "112") (name "unconnected-(U_BNO-Reserved-Pad21)") (class "Default")
      (node (ref "U_BNO") (pin "21") (pinfunction "Reserved_21") (pintype "passive"))
    )
    (net (code "113") (name "unconnected-(U_BNO-Reserved-Pad22)") (class "Default")
      (node (ref "U_BNO") (pin "22") (pinfunction "Reserved_22") (pintype "passive"))
    )
    (net (code "114") (name "unconnected-(U_BNO-Reserved-Pad23)") (class "Default")
      (node (ref "U_BNO") (pin "23") (pinfunction "Reserved_23") (pintype "passive"))
    )
    (net (code "115") (name "unconnected-(U_BNO-Reserved-Pad24)") (class "Default")
      (node (ref "U_BNO") (pin "24") (pinfunction "Reserved_24") (pintype "passive"))
    )
    (net (code "116") (name "unconnected-(U_BNO-XIN32-Pad27)") (class "Default")
      (node (ref "U_BNO") (pin "27") (pinfunction "XIN32_27") (pintype "input"))
    )
    (net (code "117") (name "unconnected-(U_TPS1-PG-Pad5)") (class "Default")
      (node (ref "U_TPS1") (pin "5") (pinfunction "PG_5") (pintype "output"))
    )
  )
)
